# assignment3.net
KiCad netlist of a schematic drawn in EAGLE
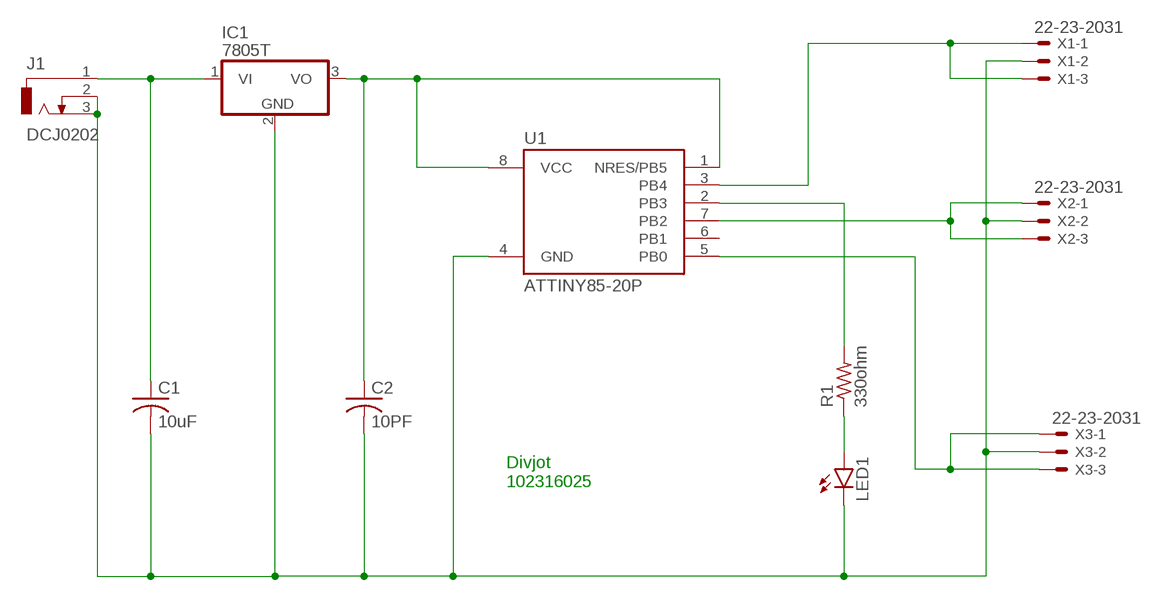
[diagram p0: schematic, sheet 1]

(export (version "E")
  (design (tool "Eeschema 10.0.6"))
  (components
    (comp (ref "C1")
      (value "10uF")
      (footprint "eagle-import:C025-024X044")
      (libsource (lib "eagle-import") (part "C-US025-024X044"))
    )
    (comp (ref "C2")
      (value "10PF")
      (footprint "eagle-import:C025-024X044")
      (libsource (lib "eagle-import") (part "C-US025-024X044"))
    )
    (comp (ref "IC1")
      (value "7805T")
      (footprint "eagle-import:TO220H")
      (libsource (lib "eagle-import") (part "78T05"))
    )
    (comp (ref "J1")
      (value "DCJ0202")
      (footprint "eagle-import:DCJ0202")
      (libsource (lib "eagle-import") (part "DCJ0202"))
    )
    (comp (ref "LED1")
      (value "LED3MM")
      (footprint "eagle-import:LED3MM")
      (libsource (lib "eagle-import") (part "LED3MM"))
    )
    (comp (ref "R1")
      (value "330ohm")
      (footprint "eagle-import:0207_5V")
      (libsource (lib "eagle-import") (part "R-US_0207/5V"))
    )
    (comp (ref "U1")
      (value "ATTINY85-20P")
      (footprint "eagle-import:PDIP08_300MIL")
      (libsource (lib "eagle-import") (part "ATTINY85P-20"))
    )
    (comp (ref "X1")
      (value "22-23-2031")
      (footprint "eagle-import:22-23-2031")
      (fields (field (name "MF") "MOLEX"))
      (libsource (lib "eagle-import") (part "22-23-2031"))
    )
    (comp (ref "X2")
      (value "22-23-2031")
      (footprint "eagle-import:22-23-2031")
      (fields (field (name "MF") "MOLEX"))
      (libsource (lib "eagle-import") (part "22-23-2031"))
    )
    (comp (ref "X3")
      (value "22-23-2031")
      (footprint "eagle-import:22-23-2031")
      (fields (field (name "MF") "MOLEX"))
      (libsource (lib "eagle-import") (part "22-23-2031"))
    )
  )
  (nets
    (net (code "1") (name "Net-(IC1-GND)") (class "Default")
      (node (ref "C1") (pin "2") (pinfunction "2_2") (pintype "passive"))
      (node (ref "C2") (pin "2") (pinfunction "2_2") (pintype "passive"))
      (node (ref "IC1") (pin "2") (pinfunction "GND_2") (pintype "passive"))
      (node (ref "J1") (pin "2") (pinfunction "2_2") (pintype "passive"))
      (node (ref "J1") (pin "3") (pinfunction "3_3") (pintype "passive"))
      (node (ref "LED1") (pin "K") (pinfunction "C_K") (pintype "passive"))
      (node (ref "U1") (pin "4") (pinfunction "GND_4") (pintype "power_in"))
      (node (ref "X1") (pin "2") (pinfunction "S_2") (pintype "passive"))
      (node (ref "X2") (pin "2") (pinfunction "S_2") (pintype "passive"))
      (node (ref "X3") (pin "2") (pinfunction "S_2") (pintype "passive"))
    )
    (net (code "2") (name "Net-(IC1-VI)") (class "Default")
      (node (ref "C1") (pin "1") (pinfunction "1_1") (pintype "passive"))
      (node (ref "IC1") (pin "1") (pinfunction "VI_1") (pintype "input"))
      (node (ref "J1") (pin "1") (pinfunction "1_1") (pintype "passive"))
    )
    (net (code "3") (name "Net-(IC1-VO)") (class "Default")
      (node (ref "C2") (pin "1") (pinfunction "1_1") (pintype "passive"))
      (node (ref "IC1") (pin "3") (pinfunction "VO_3") (pintype "passive"))
      (node (ref "U1") (pin "1") (pinfunction "NRES/PB5_1") (pintype "bidirectional"))
      (node (ref "U1") (pin "8") (pinfunction "VCC_8") (pintype "power_in"))
    )
    (net (code "4") (name "Net-(LED1-PadA)") (class "Default")
      (node (ref "LED1") (pin "A") (pinfunction "A_A") (pintype "passive"))
      (node (ref "R1") (pin "1") (pinfunction "1_1") (pintype "passive"))
    )
    (net (code "5") (name "Net-(U1-PB0)") (class "Default")
      (node (ref "U1") (pin "5") (pinfunction "PB0_5") (pintype "bidirectional"))
      (node (ref "X3") (pin "1") (pinfunction "S_1") (pintype "passive"))
      (node (ref "X3") (pin "3") (pinfunction "S_3") (pintype "passive"))
    )
    (net (code "6") (name "Net-(U1-PB2)") (class "Default")
      (node (ref "U1") (pin "7") (pinfunction "PB2_7") (pintype "bidirectional"))
      (node (ref "X2") (pin "1") (pinfunction "S_1") (pintype "passive"))
      (node (ref "X2") (pin "3") (pinfunction "S_3") (pintype "passive"))
    )
    (net (code "7") (name "Net-(U1-PB3)") (class "Default")
      (node (ref "R1") (pin "2") (pinfunction "2_2") (pintype "passive"))
      (node (ref "U1") (pin "2") (pinfunction "PB3_2") (pintype "bidirectional"))
    )
    (net (code "8") (name "Net-(U1-PB4)") (class "Default")
      (node (ref "U1") (pin "3") (pinfunction "PB4_3") (pintype "bidirectional"))
      (node (ref "X1") (pin "1") (pinfunction "S_1") (pintype "passive"))
      (node (ref "X1") (pin "3") (pinfunction "S_3") (pintype "passive"))
    )
    (net (code "9") (name "unconnected-(U1-PB1-Pad6)") (class "Default")
      (node (ref "U1") (pin "6") (pinfunction "PB1_6") (pintype "bidirectional"))
    )
  )
)
